# mickey2440.net
KiCad netlist of a schematic drawn in Altium Designer
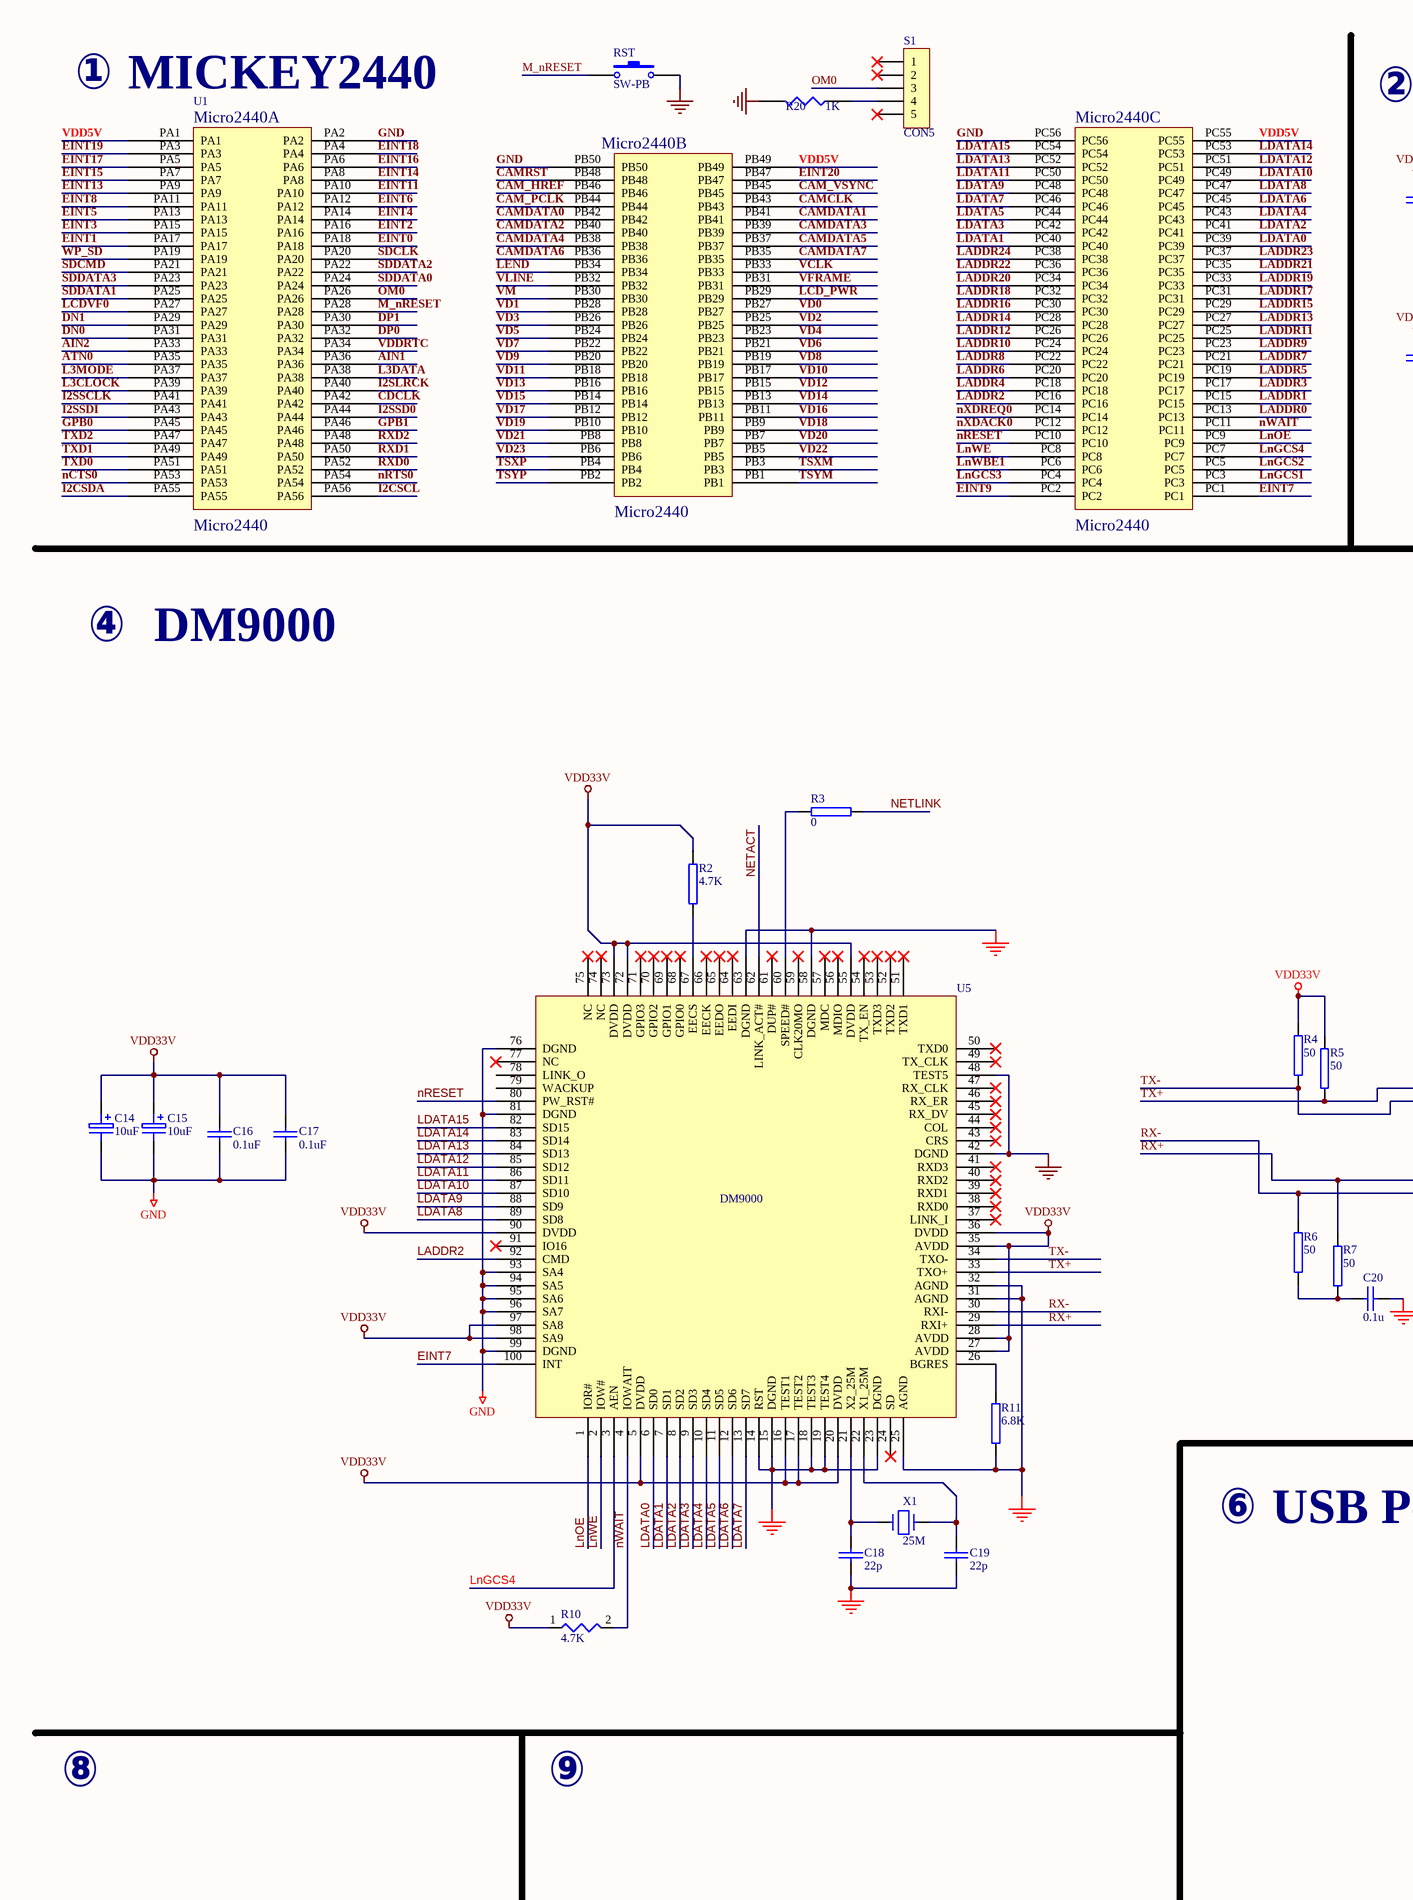
[diagram p0: mickey2440.SchDoc, left]
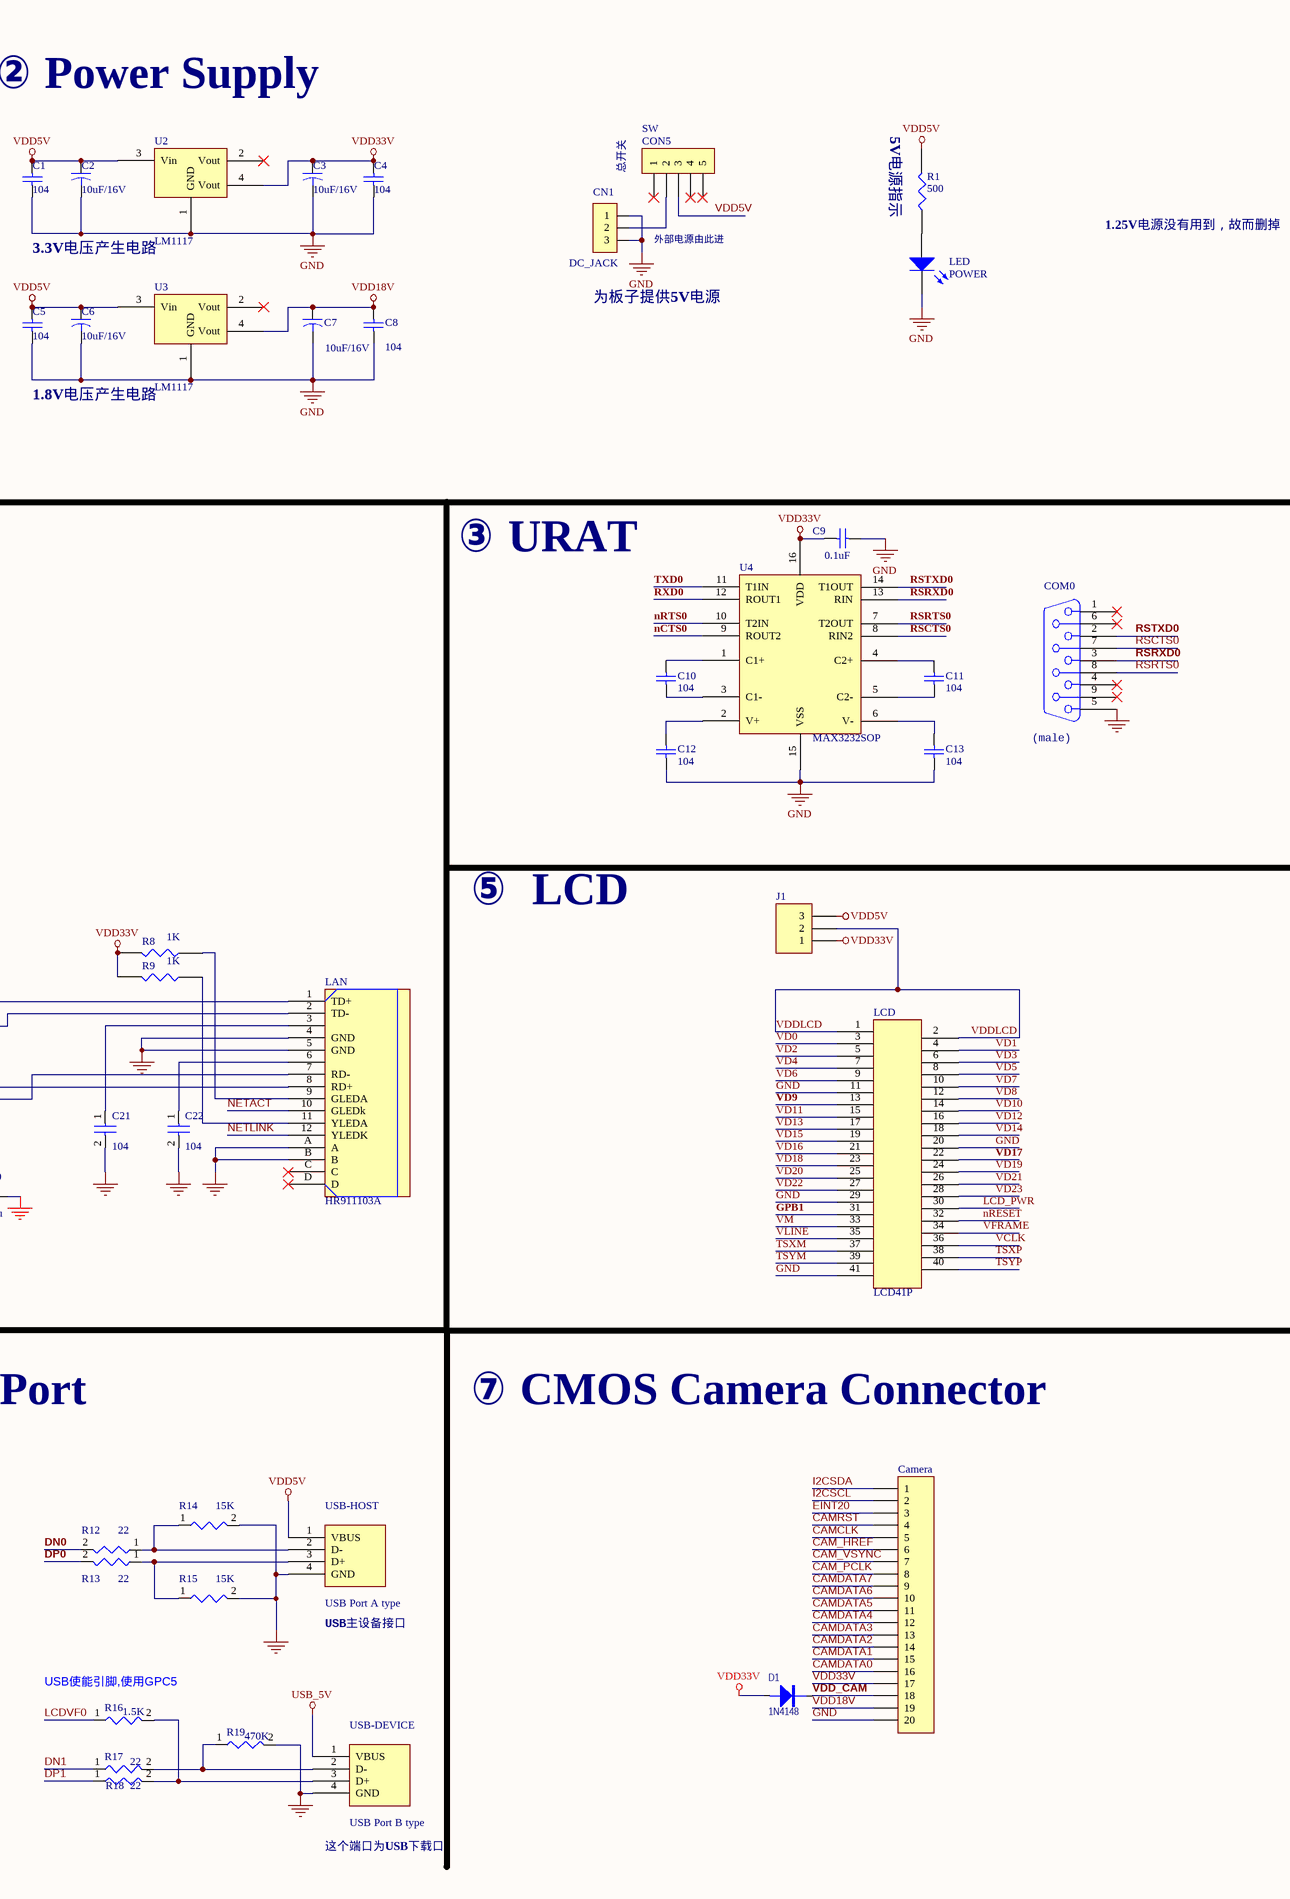
[diagram p1: mickey2440.SchDoc, right]

(export (version "E")
  (design (tool "Eeschema 10.0.6"))
  (components
    (comp (ref "C1")
      (value "104")
      (footprint "0603A")
      (description "Capacitor")
      (fields (field (name "Comment") "Cap") (field (name "PUBLISHER") "Altium Limited"))
      (libsource (lib "Miscellaneous Devices") (part "Cap"))
    )
    (comp (ref "C2")
      (value "10uF/16V")
      (footprint "C3216")
      (description "Capacitor")
      (fields (field (name "Comment") "Cap2") (field (name "PUBLISHER") "Altium Limited"))
      (libsource (lib "Miscellaneous Devices") (part "Cap2"))
    )
    (comp (ref "C3")
      (value "10uF/16V")
      (footprint "C3216")
      (description "Capacitor")
      (fields (field (name "Comment") "Cap2") (field (name "PUBLISHER") "Altium Limited"))
      (libsource (lib "Miscellaneous Devices") (part "Cap2"))
    )
    (comp (ref "C4")
      (value "104")
      (footprint "0603A")
      (description "Capacitor")
      (fields (field (name "Comment") "Cap") (field (name "PUBLISHER") "Altium Limited"))
      (libsource (lib "Miscellaneous Devices") (part "Cap"))
    )
    (comp (ref "C5")
      (value "104")
      (footprint "0603A")
      (description "Capacitor")
      (fields (field (name "Comment") "Cap") (field (name "PUBLISHER") "Altium Limited"))
      (libsource (lib "Miscellaneous Devices") (part "Cap"))
    )
    (comp (ref "C6")
      (value "10uF/16V")
      (footprint "C3216")
      (description "Capacitor")
      (fields (field (name "Comment") "Cap2") (field (name "PUBLISHER") "Altium Limited"))
      (libsource (lib "Miscellaneous Devices") (part "Cap2"))
    )
    (comp (ref "C7")
      (value "10uF/16V")
      (footprint "C3216")
      (description "Capacitor")
      (fields (field (name "Comment") "Cap2") (field (name "PUBLISHER") "Altium Limited"))
      (libsource (lib "Miscellaneous Devices") (part "Cap2"))
    )
    (comp (ref "C8")
      (value "104")
      (footprint "0603A")
      (description "Capacitor")
      (fields (field (name "Comment") "Cap") (field (name "PUBLISHER") "Altium Limited"))
      (libsource (lib "Miscellaneous Devices") (part "Cap"))
    )
    (comp (ref "C9")
      (value "0.1uF")
      (footprint "0603A")
      (description "Capacitor (Semiconductor SIM Model)")
      (fields (field (name "Comment") "Cap Semi") (field (name "PUBLISHER") "Altium Limited"))
      (libsource (lib "Miscellaneous Devices") (part "Cap Semi"))
    )
    (comp (ref "C10")
      (value "104")
      (footprint "0603A")
      (description "Capacitor (Semiconductor SIM Model)")
      (fields (field (name "Comment") "Cap Semi") (field (name "PUBLISHER") "Altium Limited"))
      (libsource (lib "Miscellaneous Devices") (part "Cap Semi"))
    )
    (comp (ref "C11")
      (value "104")
      (footprint "0603A")
      (description "Capacitor (Semiconductor SIM Model)")
      (fields (field (name "Comment") "Cap Semi") (field (name "PUBLISHER") "Altium Limited"))
      (libsource (lib "Miscellaneous Devices") (part "Cap Semi"))
    )
    (comp (ref "C12")
      (value "104")
      (footprint "0603A")
      (description "Capacitor (Semiconductor SIM Model)")
      (fields (field (name "Comment") "Cap Semi") (field (name "PUBLISHER") "Altium Limited"))
      (libsource (lib "Miscellaneous Devices") (part "Cap Semi"))
    )
    (comp (ref "C13")
      (value "104")
      (footprint "0603A")
      (description "Capacitor (Semiconductor SIM Model)")
      (fields (field (name "Comment") "Cap Semi") (field (name "PUBLISHER") "Altium Limited"))
      (libsource (lib "Miscellaneous Devices") (part "Cap Semi"))
    )
    (comp (ref "C14") (value "10uF") (footprint "C3216") (libsource (lib "*") (part "ELECTRO1")))
    (comp (ref "C15") (value "10uF") (footprint "C3216") (libsource (lib "*") (part "ELECTRO1")))
    (comp (ref "C16") (value "0.1uF") (footprint "0603A") (libsource (lib "*") (part "CAP")))
    (comp (ref "C17") (value "0.1uF") (footprint "0603A") (libsource (lib "*") (part "CAP")))
    (comp (ref "C18") (value "22p") (footprint "0603A") (libsource (lib "*") (part "CAP")))
    (comp (ref "C19") (value "22p") (footprint "0603A") (libsource (lib "*") (part "CAP")))
    (comp (ref "C20") (value "0.1u") (footprint "0603A") (libsource (lib "*") (part "CAP")))
    (comp (ref "C21") (value "104") (footprint "0603A") (libsource (lib "*") (part "CAP NP_0")))
    (comp (ref "C22") (value "104") (footprint "0603A") (libsource (lib "*") (part "CAP NP_0")))
    (comp (ref "Camera")
      (value "CON20")
      (footprint "IDC20SS")
      (description "Connector")
      (libsource (lib "*") (part "CON20"))
    )
    (comp (ref "CN1") (value "DC_JACK") (footprint "DC25") (libsource (lib "*") (part "CON3")))
    (comp (ref "COM0") (value "~") (footprint "DB9RA/M") (libsource (lib "*") (part "CONNECTOR DB9")))
    (comp (ref "D1") (value "1N4148") (footprint "D1206") (libsource (lib "*") (part "DIODE")))
    (comp (ref "J1")
      (value "~")
      (footprint "HDR1X3")
      (description "Header, 3-Pin")
      (fields (field (name "PUBLISHER") "Altium Limited"))
      (libsource (lib "Miscellaneous Connectors") (part "Header 3"))
    )
    (comp (ref "LAN") (value "HR911103A") (footprint "HR911103A") (libsource (lib "*") (part "HR911103A")))
    (comp (ref "LCD") (value "LCD41P") (footprint "DF9B-41P-1V2") (libsource (lib "*") (part "LCD41P")))
    (comp (ref "LED")
      (value "POWER")
      (footprint "LED")
      (description "Typical BLUE SiC LED")
      (fields (field (name "PUBLISHER") "Altium Limited"))
      (libsource (lib "Miscellaneous Devices") (part "LED3"))
    )
    (comp (ref "R1") (value "500") (footprint "0603R") (libsource (lib "*") (part "RES1")))
    (comp (ref "R2") (value "4.7K") (footprint "0603R") (libsource (lib "*") (part "RES2")))
    (comp (ref "R3") (value "0") (footprint "0603R") (libsource (lib "*") (part "RES2")))
    (comp (ref "R4") (value "50") (footprint "0603R") (libsource (lib "*") (part "RES2")))
    (comp (ref "R5") (value "50") (footprint "0603R") (libsource (lib "*") (part "RES2")))
    (comp (ref "R6") (value "50") (footprint "0603R") (libsource (lib "*") (part "RES2")))
    (comp (ref "R7") (value "50") (footprint "0603R") (libsource (lib "*") (part "RES2")))
    (comp (ref "R8") (value "1K") (footprint "0603R") (libsource (lib "*") (part "RES1")))
    (comp (ref "R9") (value "1K") (footprint "0603R") (libsource (lib "*") (part "RES1")))
    (comp (ref "R10") (value "4.7K") (footprint "0603R") (libsource (lib "*") (part "R_0")))
    (comp (ref "R11") (value "6.8K") (footprint "0603R") (libsource (lib "*") (part "RES2")))
    (comp (ref "R12") (value "22") (footprint "0603R") (libsource (lib "*") (part "RESISTOR_2")))
    (comp (ref "R13") (value "22") (footprint "0603R") (libsource (lib "*") (part "RESISTOR_2")))
    (comp (ref "R14") (value "15K") (footprint "0603R") (libsource (lib "*") (part "RESISTOR_2")))
    (comp (ref "R15") (value "15K") (footprint "0603R") (libsource (lib "*") (part "RESISTOR_2")))
    (comp (ref "R16") (value "1.5K") (footprint "0603R") (libsource (lib "*") (part "RESISTOR_2")))
    (comp (ref "R17") (value "22") (footprint "0603R") (libsource (lib "*") (part "RESISTOR_2")))
    (comp (ref "R18") (value "22") (footprint "0603R") (libsource (lib "*") (part "RESISTOR_2")))
    (comp (ref "R19") (value "470K") (footprint "0603R") (libsource (lib "*") (part "RESISTOR_2")))
    (comp (ref "R20") (value "1K") (footprint "0603R") (libsource (lib "*") (part "RES1")))
    (comp (ref "RST")
      (value "SW-PB")
      (footprint "RST")
      (description "Switch")
      (fields (field (name "PUBLISHER") "Altium Limited"))
      (libsource (lib "Miscellaneous Devices") (part "SW-PB"))
    )
    (comp (ref "S1")
      (value "CON5")
      (footprint "PCBComponent_1")
      (description "Connector")
      (libsource (lib "*") (part "CON5"))
    )
    (comp (ref "SW")
      (value "CON5")
      (footprint "Micro2440_LIB:PCBComponent_1")
      (description "Connector")
      (libsource (lib "") (part "CON5_1"))
    )
    (comp (ref "U1")
      (value "Micro2440")
      (footprint "Micro2440SDK:MICRO2440")
      (libsource (lib "MICRO2440_01") (part "Component_1"))
    )
    (comp (ref "U2")
      (value "LM1117")
      (footprint "2440_LIB:SOT223S")
      (libsource (lib "MICRO2440_LIB") (part "LM1117"))
    )
    (comp (ref "U3") (value "LM1117") (footprint "SOT223S") (libsource (lib "MICRO2440_LIB") (part "LM1117")))
    (comp (ref "U4")
      (value "MAX3232SOP")
      (footprint "SSOP16")
      (libsource (lib "MAX3232SOP") (part "Component_1"))
    )
    (comp (ref "U5") (value "DM9000") (footprint "QFP100") (libsource (lib "*") (part "DM9000")))
    (comp (ref "USB-DEVICE")
      (value "USB Port B type")
      (footprint "USB-B")
      (libsource (lib "*") (part "USBPORT"))
    )
    (comp (ref "USB-HOST")
      (value "USB Port A type")
      (footprint "USB-A")
      (libsource (lib "*") (part "USBPORT"))
    )
    (comp (ref "X1") (value "25M") (footprint "OSC2PR-1") (libsource (lib "*") (part "CRYSTAL")))
  )
  (nets
    (net (code "1") (name "/AIN1") (class "Default")
      (node (ref "U1") (pin "PA36") (pinfunction "PA36_PA36") (pintype "passive"))
    )
    (net (code "2") (name "/AIN2") (class "Default")
      (node (ref "U1") (pin "PA33") (pinfunction "PA33_PA33") (pintype "passive"))
    )
    (net (code "3") (name "/ATN0") (class "Default")
      (node (ref "U1") (pin "PA35") (pinfunction "PA35_PA35") (pintype "passive"))
    )
    (net (code "4") (name "/CAMCLK") (class "Default")
      (node (ref "Camera") (pin "5") (pinfunction "5_5") (pintype "passive"))
      (node (ref "U1") (pin "PB43") (pinfunction "PB43_PB43") (pintype "passive"))
    )
    (net (code "5") (name "/CAMDATA0") (class "Default")
      (node (ref "Camera") (pin "16") (pinfunction "16_16") (pintype "passive"))
      (node (ref "U1") (pin "PB42") (pinfunction "PB42_PB42") (pintype "passive"))
    )
    (net (code "6") (name "/CAMDATA1") (class "Default")
      (node (ref "Camera") (pin "15") (pinfunction "15_15") (pintype "passive"))
      (node (ref "U1") (pin "PB41") (pinfunction "PB41_PB41") (pintype "passive"))
    )
    (net (code "7") (name "/CAMDATA2") (class "Default")
      (node (ref "Camera") (pin "14") (pinfunction "14_14") (pintype "passive"))
      (node (ref "U1") (pin "PB40") (pinfunction "PB40_PB40") (pintype "passive"))
    )
    (net (code "8") (name "/CAMDATA3") (class "Default")
      (node (ref "Camera") (pin "13") (pinfunction "13_13") (pintype "passive"))
      (node (ref "U1") (pin "PB39") (pinfunction "PB39_PB39") (pintype "passive"))
    )
    (net (code "9") (name "/CAMDATA4") (class "Default")
      (node (ref "Camera") (pin "12") (pinfunction "12_12") (pintype "passive"))
      (node (ref "U1") (pin "PB38") (pinfunction "PB38_PB38") (pintype "passive"))
    )
    (net (code "10") (name "/CAMDATA5") (class "Default")
      (node (ref "Camera") (pin "11") (pinfunction "11_11") (pintype "passive"))
      (node (ref "U1") (pin "PB37") (pinfunction "PB37_PB37") (pintype "passive"))
    )
    (net (code "11") (name "/CAMDATA6") (class "Default")
      (node (ref "Camera") (pin "10") (pinfunction "10_10") (pintype "passive"))
      (node (ref "U1") (pin "PB36") (pinfunction "PB36_PB36") (pintype "passive"))
    )
    (net (code "12") (name "/CAMDATA7") (class "Default")
      (node (ref "Camera") (pin "9") (pinfunction "9_9") (pintype "passive"))
      (node (ref "U1") (pin "PB35") (pinfunction "PB35_PB35") (pintype "passive"))
    )
    (net (code "13") (name "/CAMRST") (class "Default")
      (node (ref "Camera") (pin "4") (pinfunction "4_4") (pintype "passive"))
      (node (ref "U1") (pin "PB48") (pinfunction "PB48_PB48") (pintype "passive"))
    )
    (net (code "14") (name "/CAM_HREF") (class "Default")
      (node (ref "Camera") (pin "6") (pinfunction "6_6") (pintype "passive"))
      (node (ref "U1") (pin "PB46") (pinfunction "PB46_PB46") (pintype "passive"))
    )
    (net (code "15") (name "/CAM_PCLK") (class "Default")
      (node (ref "Camera") (pin "8") (pinfunction "8_8") (pintype "passive"))
      (node (ref "U1") (pin "PB44") (pinfunction "PB44_PB44") (pintype "passive"))
    )
    (net (code "16") (name "/CAM_VSYNC") (class "Default")
      (node (ref "Camera") (pin "7") (pinfunction "7_7") (pintype "passive"))
      (node (ref "U1") (pin "PB45") (pinfunction "PB45_PB45") (pintype "passive"))
    )
    (net (code "17") (name "/CDCLK") (class "Default")
      (node (ref "U1") (pin "PA42") (pinfunction "PA42_PA42") (pintype "passive"))
    )
    (net (code "18") (name "/DN0") (class "Default")
      (node (ref "R12") (pin "2") (pinfunction "2_2") (pintype "passive"))
      (node (ref "U1") (pin "PA31") (pinfunction "PA31_PA31") (pintype "passive"))
    )
    (net (code "19") (name "/DN1") (class "Default")
      (node (ref "R17") (pin "1") (pinfunction "1_1") (pintype "passive"))
      (node (ref "U1") (pin "PA29") (pinfunction "PA29_PA29") (pintype "passive"))
    )
    (net (code "20") (name "/DP0") (class "Default")
      (node (ref "R13") (pin "2") (pinfunction "2_2") (pintype "passive"))
      (node (ref "U1") (pin "PA32") (pinfunction "PA32_PA32") (pintype "passive"))
    )
    (net (code "21") (name "/DP1") (class "Default")
      (node (ref "R18") (pin "1") (pinfunction "1_1") (pintype "passive"))
      (node (ref "U1") (pin "PA30") (pinfunction "PA30_PA30") (pintype "passive"))
    )
    (net (code "22") (name "/EINT0") (class "Default")
      (node (ref "U1") (pin "PA18") (pinfunction "PA18_PA18") (pintype "passive"))
    )
    (net (code "23") (name "/EINT1") (class "Default")
      (node (ref "U1") (pin "PA17") (pinfunction "PA17_PA17") (pintype "passive"))
    )
    (net (code "24") (name "/EINT2") (class "Default")
      (node (ref "U1") (pin "PA16") (pinfunction "PA16_PA16") (pintype "passive"))
    )
    (net (code "25") (name "/EINT3") (class "Default")
      (node (ref "U1") (pin "PA15") (pinfunction "PA15_PA15") (pintype "passive"))
    )
    (net (code "26") (name "/EINT4") (class "Default")
      (node (ref "U1") (pin "PA14") (pinfunction "PA14_PA14") (pintype "passive"))
    )
    (net (code "27") (name "/EINT5") (class "Default")
      (node (ref "U1") (pin "PA13") (pinfunction "PA13_PA13") (pintype "passive"))
    )
    (net (code "28") (name "/EINT6") (class "Default")
      (node (ref "U1") (pin "PA12") (pinfunction "PA12_PA12") (pintype "passive"))
    )
    (net (code "29") (name "/EINT7") (class "Default")
      (node (ref "U1") (pin "PC1") (pinfunction "PC1_PC1") (pintype "passive"))
      (node (ref "U5") (pin "100") (pinfunction "INT_100") (pintype "passive"))
    )
    (net (code "30") (name "/EINT8") (class "Default")
      (node (ref "U1") (pin "PA11") (pinfunction "PA11_PA11") (pintype "passive"))
    )
    (net (code "31") (name "/EINT9") (class "Default")
      (node (ref "U1") (pin "PC2") (pinfunction "PC2_PC2") (pintype "passive"))
    )
    (net (code "32") (name "/EINT11") (class "Default")
      (node (ref "U1") (pin "PA10") (pinfunction "PA10_PA10") (pintype "passive"))
    )
    (net (code "33") (name "/EINT13") (class "Default")
      (node (ref "U1") (pin "PA9") (pinfunction "PA9_PA9") (pintype "passive"))
    )
    (net (code "34") (name "/EINT14") (class "Default")
      (node (ref "U1") (pin "PA8") (pinfunction "PA8_PA8") (pintype "passive"))
    )
    (net (code "35") (name "/EINT15") (class "Default")
      (node (ref "U1") (pin "PA7") (pinfunction "PA7_PA7") (pintype "passive"))
    )
    (net (code "36") (name "/EINT16") (class "Default")
      (node (ref "U1") (pin "PA6") (pinfunction "PA6_PA6") (pintype "passive"))
    )
    (net (code "37") (name "/EINT17") (class "Default")
      (node (ref "U1") (pin "PA5") (pinfunction "PA5_PA5") (pintype "passive"))
    )
    (net (code "38") (name "/EINT18") (class "Default")
      (node (ref "U1") (pin "PA4") (pinfunction "PA4_PA4") (pintype "passive"))
    )
    (net (code "39") (name "/EINT19") (class "Default")
      (node (ref "U1") (pin "PA3") (pinfunction "PA3_PA3") (pintype "passive"))
    )
    (net (code "40") (name "/EINT20") (class "Default")
      (node (ref "Camera") (pin "3") (pinfunction "3_3") (pintype "passive"))
      (node (ref "U1") (pin "PB47") (pinfunction "PB47_PB47") (pintype "passive"))
    )
    (net (code "41") (name "/GPB0") (class "Default")
      (node (ref "U1") (pin "PA45") (pinfunction "PA45_PA45") (pintype "passive"))
    )
    (net (code "42") (name "/GPB1") (class "Default")
      (node (ref "LCD") (pin "31") (pintype "passive"))
      (node (ref "U1") (pin "PA46") (pinfunction "PA46_PA46") (pintype "passive"))
    )
    (net (code "43") (name "/I2CSCL") (class "Default")
      (node (ref "Camera") (pin "2") (pinfunction "2_2") (pintype "passive"))
      (node (ref "U1") (pin "PA56") (pinfunction "PA56_PA56") (pintype "passive"))
    )
    (net (code "44") (name "/I2CSDA") (class "Default")
      (node (ref "Camera") (pin "1") (pinfunction "1_1") (pintype "passive"))
      (node (ref "U1") (pin "PA55") (pinfunction "PA55_PA55") (pintype "passive"))
    )
    (net (code "45") (name "/I2SLRCK") (class "Default")
      (node (ref "U1") (pin "PA40") (pinfunction "PA40_PA40") (pintype "passive"))
    )
    (net (code "46") (name "/I2SSCLK") (class "Default")
      (node (ref "U1") (pin "PA41") (pinfunction "PA41_PA41") (pintype "passive"))
    )
    (net (code "47") (name "/I2SSD0") (class "Default")
      (node (ref "U1") (pin "PA44") (pinfunction "PA44_PA44") (pintype "passive"))
    )
    (net (code "48") (name "/I2SSDI") (class "Default")
      (node (ref "U1") (pin "PA43") (pinfunction "PA43_PA43") (pintype "passive"))
    )
    (net (code "49") (name "/L3CLOCK") (class "Default")
      (node (ref "U1") (pin "PA39") (pinfunction "PA39_PA39") (pintype "passive"))
    )
    (net (code "50") (name "/L3DATA") (class "Default")
      (node (ref "U1") (pin "PA38") (pinfunction "PA38_PA38") (pintype "passive"))
    )
    (net (code "51") (name "/L3MODE") (class "Default")
      (node (ref "U1") (pin "PA37") (pinfunction "PA37_PA37") (pintype "passive"))
    )
    (net (code "52") (name "/LADDR0") (class "Default")
      (node (ref "U1") (pin "PC13") (pinfunction "PC13_PC13") (pintype "passive"))
    )
    (net (code "53") (name "/LADDR1") (class "Default")
      (node (ref "U1") (pin "PC15") (pinfunction "PC15_PC15") (pintype "passive"))
    )
    (net (code "54") (name "/LADDR2") (class "Default")
      (node (ref "U1") (pin "PC16") (pinfunction "PC16_PC16") (pintype "passive"))
      (node (ref "U5") (pin "92") (pinfunction "CMD_92") (pintype "passive"))
    )
    (net (code "55") (name "/LADDR3") (class "Default")
      (node (ref "U1") (pin "PC17") (pinfunction "PC17_PC17") (pintype "passive"))
    )
    (net (code "56") (name "/LADDR4") (class "Default")
      (node (ref "U1") (pin "PC18") (pinfunction "PC18_PC18") (pintype "passive"))
    )
    (net (code "57") (name "/LADDR5") (class "Default")
      (node (ref "U1") (pin "PC19") (pinfunction "PC19_PC19") (pintype "passive"))
    )
    (net (code "58") (name "/LADDR6") (class "Default")
      (node (ref "U1") (pin "PC20") (pinfunction "PC20_PC20") (pintype "passive"))
    )
    (net (code "59") (name "/LADDR7") (class "Default")
      (node (ref "U1") (pin "PC21") (pinfunction "PC21_PC21") (pintype "passive"))
    )
    (net (code "60") (name "/LADDR8") (class "Default")
      (node (ref "U1") (pin "PC22") (pinfunction "PC22_PC22") (pintype "passive"))
    )
    (net (code "61") (name "/LADDR9") (class "Default")
      (node (ref "U1") (pin "PC23") (pinfunction "PC23_PC23") (pintype "passive"))
    )
    (net (code "62") (name "/LADDR10") (class "Default")
      (node (ref "U1") (pin "PC24") (pinfunction "PC24_PC24") (pintype "passive"))
    )
    (net (code "63") (name "/LADDR11") (class "Default")
      (node (ref "U1") (pin "PC25") (pinfunction "PC25_PC25") (pintype "passive"))
    )
    (net (code "64") (name "/LADDR12") (class "Default")
      (node (ref "U1") (pin "PC26") (pinfunction "PC26_PC26") (pintype "passive"))
    )
    (net (code "65") (name "/LADDR13") (class "Default")
      (node (ref "U1") (pin "PC27") (pinfunction "PC27_PC27") (pintype "passive"))
    )
    (net (code "66") (name "/LADDR14") (class "Default")
      (node (ref "U1") (pin "PC28") (pinfunction "PC28_PC28") (pintype "passive"))
    )
    (net (code "67") (name "/LADDR15") (class "Default")
      (node (ref "U1") (pin "PC29") (pinfunction "PC29_PC29") (pintype "passive"))
    )
    (net (code "68") (name "/LADDR16") (class "Default")
      (node (ref "U1") (pin "PC30") (pinfunction "PC30_PC30") (pintype "passive"))
    )
    (net (code "69") (name "/LADDR17") (class "Default")
      (node (ref "U1") (pin "PC31") (pinfunction "PC31_PC31") (pintype "passive"))
    )
    (net (code "70") (name "/LADDR18") (class "Default")
      (node (ref "U1") (pin "PC32") (pinfunction "PC32_PC32") (pintype "passive"))
    )
    (net (code "71") (name "/LADDR19") (class "Default")
      (node (ref "U1") (pin "PC33") (pinfunction "PC33_PC33") (pintype "passive"))
    )
    (net (code "72") (name "/LADDR20") (class "Default")
      (node (ref "U1") (pin "PC34") (pinfunction "PC34_PC34") (pintype "passive"))
    )
    (net (code "73") (name "/LADDR21") (class "Default")
      (node (ref "U1") (pin "PC35") (pinfunction "PC35_PC35") (pintype "passive"))
    )
    (net (code "74") (name "/LADDR22") (class "Default")
      (node (ref "U1") (pin "PC36") (pinfunction "PC36_PC36") (pintype "passive"))
    )
    (net (code "75") (name "/LADDR23") (class "Default")
      (node (ref "U1") (pin "PC37") (pinfunction "PC37_PC37") (pintype "passive"))
    )
    (net (code "76") (name "/LADDR24") (class "Default")
      (node (ref "U1") (pin "PC38") (pinfunction "PC38_PC38") (pintype "passive"))
    )
    (net (code "77") (name "/LCDVF0") (class "Default")
      (node (ref "R16") (pin "1") (pinfunction "1_1") (pintype "passive"))
      (node (ref "U1") (pin "PA27") (pinfunction "PA27_PA27") (pintype "passive"))
    )
    (net (code "78") (name "/LCD_PWR") (class "Default")
      (node (ref "LCD") (pin "30") (pintype "passive"))
      (node (ref "U1") (pin "PB29") (pinfunction "PB29_PB29") (pintype "passive"))
    )
    (net (code "79") (name "/LDATA0") (class "Default")
      (node (ref "U1") (pin "PC39") (pinfunction "PC39_PC39") (pintype "passive"))
      (node (ref "U5") (pin "6") (pinfunction "SD0_6") (pintype "passive"))
    )
    (net (code "80") (name "/LDATA1") (class "Default")
      (node (ref "U1") (pin "PC40") (pinfunction "PC40_PC40") (pintype "passive"))
      (node (ref "U5") (pin "7") (pinfunction "SD1_7") (pintype "passive"))
    )
    (net (code "81") (name "/LDATA2") (class "Default")
      (node (ref "U1") (pin "PC41") (pinfunction "PC41_PC41") (pintype "passive"))
      (node (ref "U5") (pin "8") (pinfunction "SD2_8") (pintype "passive"))
    )
    (net (code "82") (name "/LDATA3") (class "Default")
      (node (ref "U1") (pin "PC42") (pinfunction "PC42_PC42") (pintype "passive"))
      (node (ref "U5") (pin "9") (pinfunction "SD3_9") (pintype "passive"))
    )
    (net (code "83") (name "/LDATA4") (class "Default")
      (node (ref "U1") (pin "PC43") (pinfunction "PC43_PC43") (pintype "passive"))
      (node (ref "U5") (pin "10") (pinfunction "SD4_10") (pintype "passive"))
    )
    (net (code "84") (name "/LDATA5") (class "Default")
      (node (ref "U1") (pin "PC44") (pinfunction "PC44_PC44") (pintype "passive"))
      (node (ref "U5") (pin "11") (pinfunction "SD5_11") (pintype "passive"))
    )
    (net (code "85") (name "/LDATA6") (class "Default")
      (node (ref "U1") (pin "PC45") (pinfunction "PC45_PC45") (pintype "passive"))
      (node (ref "U5") (pin "12") (pinfunction "SD6_12") (pintype "passive"))
    )
    (net (code "86") (name "/LDATA7") (class "Default")
      (node (ref "U1") (pin "PC46") (pinfunction "PC46_PC46") (pintype "passive"))
      (node (ref "U5") (pin "13") (pinfunction "SD7_13") (pintype "passive"))
    )
    (net (code "87") (name "/LDATA8") (class "Default")
      (node (ref "U1") (pin "PC47") (pinfunction "PC47_PC47") (pintype "passive"))
      (node (ref "U5") (pin "89") (pinfunction "SD8_89") (pintype "passive"))
    )
    (net (code "88") (name "/LDATA9") (class "Default")
      (node (ref "U1") (pin "PC48") (pinfunction "PC48_PC48") (pintype "passive"))
      (node (ref "U5") (pin "88") (pinfunction "SD9_88") (pintype "passive"))
    )
    (net (code "89") (name "/LDATA10") (class "Default")
      (node (ref "U1") (pin "PC49") (pinfunction "PC49_PC49") (pintype "passive"))
      (node (ref "U5") (pin "87") (pinfunction "SD10_87") (pintype "passive"))
    )
    (net (code "90") (name "/LDATA11") (class "Default")
      (node (ref "U1") (pin "PC50") (pinfunction "PC50_PC50") (pintype "passive"))
      (node (ref "U5") (pin "86") (pinfunction "SD11_86") (pintype "passive"))
    )
    (net (code "91") (name "/LDATA12") (class "Default")
      (node (ref "U1") (pin "PC51") (pinfunction "PC51_PC51") (pintype "passive"))
      (node (ref "U5") (pin "85") (pinfunction "SD12_85") (pintype "passive"))
    )
    (net (code "92") (name "/LDATA13") (class "Default")
      (node (ref "U1") (pin "PC52") (pinfunction "PC52_PC52") (pintype "passive"))
      (node (ref "U5") (pin "84") (pinfunction "SD13_84") (pintype "passive"))
    )
    (net (code "93") (name "/LDATA14") (class "Default")
      (node (ref "U1") (pin "PC53") (pinfunction "PC53_PC53") (pintype "passive"))
      (node (ref "U5") (pin "83") (pinfunction "SD14_83") (pintype "passive"))
    )
    (net (code "94") (name "/LDATA15") (class "Default")
      (node (ref "U1") (pin "PC54") (pinfunction "PC54_PC54") (pintype "passive"))
      (node (ref "U5") (pin "82") (pinfunction "SD15_82") (pintype "passive"))
    )
    (net (code "95") (name "/LEND") (class "Default")
      (node (ref "U1") (pin "PB34") (pinfunction "PB34_PB34") (pintype "passive"))
    )
    (net (code "96") (name "/LnGCS1") (class "Default")
      (node (ref "U1") (pin "PC3") (pinfunction "PC3_PC3") (pintype "passive"))
    )
    (net (code "97") (name "/LnGCS2") (class "Default")
      (node (ref "U1") (pin "PC5") (pinfunction "PC5_PC5") (pintype "passive"))
    )
    (net (code "98") (name "/LnGCS3") (class "Default")
      (node (ref "U1") (pin "PC4") (pinfunction "PC4_PC4") (pintype "passive"))
    )
    (net (code "99") (name "/LnGCS4") (class "Default")
      (node (ref "U1") (pin "PC7") (pinfunction "PC7_PC7") (pintype "passive"))
      (node (ref "U5") (pin "3") (pinfunction "AEN_3") (pintype "passive"))
    )
    (net (code "100") (name "/LnOE") (class "Default")
      (node (ref "U1") (pin "PC9") (pinfunction "PC9_PC9") (pintype "passive"))
      (node (ref "U5") (pin "1") (pinfunction "IOR#_1") (pintype "passive"))
    )
    (net (code "101") (name "/LnWBE1") (class "Default")
      (node (ref "U1") (pin "PC6") (pinfunction "PC6_PC6") (pintype "passive"))
    )
    (net (code "102") (name "/LnWE") (class "Default")
      (node (ref "U1") (pin "PC8") (pinfunction "PC8_PC8") (pintype "passive"))
      (node (ref "U5") (pin "2") (pinfunction "IOW#_2") (pintype "passive"))
    )
    (net (code "103") (name "/M_nRESET") (class "Default")
      (node (ref "RST") (pin "1") (pinfunction "1_1") (pintype "passive"))
      (node (ref "U1") (pin "PA28") (pinfunction "PA28_PA28") (pintype "passive"))
    )
    (net (code "104") (name "/NETACT") (class "Default")
      (node (ref "LAN") (pin "10") (pinfunction "GLEDk_10") (pintype "passive"))
      (node (ref "U5") (pin "62") (pinfunction "LINK_ACT#_62") (pintype "passive"))
    )
    (net (code "105") (name "/NETLINK") (class "Default")
      (node (ref "LAN") (pin "12") (pinfunction "YLEDK_12") (pintype "passive"))
      (node (ref "R3") (pin "1") (pintype "passive"))
    )
    (net (code "106") (name "/OM0") (class "Default")
      (node (ref "S1") (pin "3") (pinfunction "3_3") (pintype "passive"))
      (node (ref "U1") (pin "PA26") (pinfunction "PA26_PA26") (pintype "passive"))
    )
    (net (code "107") (name "/RSCTS0") (class "Default")
      (node (ref "COM0") (pin "7") (pinfunction "7_7") (pintype "passive"))
      (node (ref "U4") (pin "8") (pinfunction "RIN2_8") (pintype "passive"))
    )
    (net (code "108") (name "/RSRTS0") (class "Default")
      (node (ref "COM0") (pin "8") (pinfunction "8_8") (pintype "passive"))
      (node (ref "U4") (pin "7") (pinfunction "T2OUT_7") (pintype "passive"))
    )
    (net (code "109") (name "/RSRXD0") (class "Default")
      (node (ref "COM0") (pin "3") (pinfunction "3_3") (pintype "passive"))
      (node (ref "U4") (pin "13") (pinfunction "RIN_13") (pintype "passive"))
    )
    (net (code "110") (name "/RSTXD0") (class "Default")
      (node (ref "COM0") (pin "2") (pinfunction "2_2") (pintype "passive"))
      (node (ref "U4") (pin "14") (pinfunction "T1OUT_14") (pintype "passive"))
    )
    (net (code "111") (name "/RX+") (class "Default")
      (node (ref "LAN") (pin "8") (pinfunction "RD+_8") (pintype "passive"))
      (node (ref "R7") (pin "2") (pintype "passive"))
      (node (ref "U5") (pin "29") (pinfunction "RXI+_29") (pintype "passive"))
    )
    (net (code "112") (name "/RX-") (class "Default")
      (node (ref "LAN") (pin "7") (pinfunction "RD-_7") (pintype "passive"))
      (node (ref "R6") (pin "2") (pintype "passive"))
      (node (ref "U5") (pin "30") (pinfunction "RXI-_30") (pintype "passive"))
    )
    (net (code "113") (name "/RXD0") (class "Default")
      (node (ref "U1") (pin "PA52") (pinfunction "PA52_PA52") (pintype "passive"))
      (node (ref "U4") (pin "12") (pinfunction "ROUT1_12") (pintype "passive"))
    )
    (net (code "114") (name "/RXD1") (class "Default")
      (node (ref "U1") (pin "PA50") (pinfunction "PA50_PA50") (pintype "passive"))
    )
    (net (code "115") (name "/RXD2") (class "Default")
      (node (ref "U1") (pin "PA48") (pinfunction "PA48_PA48") (pintype "passive"))
    )
    (net (code "116") (name "/SDCLK") (class "Default")
      (node (ref "U1") (pin "PA20") (pinfunction "PA20_PA20") (pintype "passive"))
    )
    (net (code "117") (name "/SDCMD") (class "Default")
      (node (ref "U1") (pin "PA21") (pinfunction "PA21_PA21") (pintype "passive"))
    )
    (net (code "118") (name "/SDDATA0") (class "Default")
      (node (ref "U1") (pin "PA24") (pinfunction "PA24_PA24") (pintype "passive"))
    )
    (net (code "119") (name "/SDDATA1") (class "Default")
      (node (ref "U1") (pin "PA25") (pinfunction "PA25_PA25") (pintype "passive"))
    )
    (net (code "120") (name "/SDDATA2") (class "Default")
      (node (ref "U1") (pin "PA22") (pinfunction "PA22_PA22") (pintype "passive"))
    )
    (net (code "121") (name "/SDDATA3") (class "Default")
      (node (ref "U1") (pin "PA23") (pinfunction "PA23_PA23") (pintype "passive"))
    )
    (net (code "122") (name "/TSXM") (class "Default")
      (node (ref "LCD") (pin "37") (pintype "passive"))
      (node (ref "U1") (pin "PB3") (pinfunction "PB3_PB3") (pintype "passive"))
    )
    (net (code "123") (name "/TSXP") (class "Default")
      (node (ref "LCD") (pin "38") (pintype "passive"))
      (node (ref "U1") (pin "PB4") (pinfunction "PB4_PB4") (pintype "passive"))
    )
    (net (code "124") (name "/TSYM") (class "Default")
      (node (ref "LCD") (pin "39") (pintype "passive"))
      (node (ref "U1") (pin "PB1") (pinfunction "PB1_PB1") (pintype "passive"))
    )
    (net (code "125") (name "/TSYP") (class "Default")
      (node (ref "LCD") (pin "40") (pintype "passive"))
      (node (ref "U1") (pin "PB2") (pinfunction "PB2_PB2") (pintype "passive"))
    )
    (net (code "126") (name "/TX+") (class "Default")
      (node (ref "LAN") (pin "1") (pinfunction "TD+_1") (pintype "passive"))
      (node (ref "R5") (pin "1") (pintype "passive"))
      (node (ref "U5") (pin "33") (pinfunction "TXO+_33") (pintype "passive"))
    )
    (net (code "127") (name "/TX-") (class "Default")
      (node (ref "LAN") (pin "2") (pinfunction "TD-_2") (pintype "passive"))
      (node (ref "R4") (pin "1") (pintype "passive"))
      (node (ref "U5") (pin "34") (pinfunction "TXO-_34") (pintype "passive"))
    )
    (net (code "128") (name "/TXD0") (class "Default")
      (node (ref "U1") (pin "PA51") (pinfunction "PA51_PA51") (pintype "passive"))
      (node (ref "U4") (pin "11") (pinfunction "T1IN_11") (pintype "passive"))
    )
    (net (code "129") (name "/TXD1") (class "Default")
      (node (ref "U1") (pin "PA49") (pinfunction "PA49_PA49") (pintype "passive"))
    )
    (net (code "130") (name "/TXD2") (class "Default")
      (node (ref "U1") (pin "PA47") (pinfunction "PA47_PA47") (pintype "passive"))
    )
    (net (code "131") (name "/VCLK") (class "Default")
      (node (ref "LCD") (pin "36") (pintype "passive"))
      (node (ref "U1") (pin "PB33") (pinfunction "PB33_PB33") (pintype "passive"))
    )
    (net (code "132") (name "/VD0") (class "Default")
      (node (ref "LCD") (pin "3") (pintype "passive"))
      (node (ref "U1") (pin "PB27") (pinfunction "PB27_PB27") (pintype "passive"))
    )
    (net (code "133") (name "/VD1") (class "Default")
      (node (ref "LCD") (pin "4") (pintype "passive"))
      (node (ref "U1") (pin "PB28") (pinfunction "PB28_PB28") (pintype "passive"))
    )
    (net (code "134") (name "/VD2") (class "Default")
      (node (ref "LCD") (pin "5") (pintype "passive"))
      (node (ref "U1") (pin "PB25") (pinfunction "PB25_PB25") (pintype "passive"))
    )
    (net (code "135") (name "/VD3") (class "Default")
      (node (ref "LCD") (pin "6") (pintype "passive"))
      (node (ref "U1") (pin "PB26") (pinfunction "PB26_PB26") (pintype "passive"))
    )
    (net (code "136") (name "/VD4") (class "Default")
      (node (ref "LCD") (pin "7") (pintype "passive"))
      (node (ref "U1") (pin "PB23") (pinfunction "PB23_PB23") (pintype "passive"))
    )
    (net (code "137") (name "/VD5") (class "Default")
      (node (ref "LCD") (pin "8") (pintype "passive"))
      (node (ref "U1") (pin "PB24") (pinfunction "PB24_PB24") (pintype "passive"))
    )
    (net (code "138") (name "/VD6") (class "Default")
      (node (ref "LCD") (pin "9") (pintype "passive"))
      (node (ref "U1") (pin "PB21") (pinfunction "PB21_PB21") (pintype "passive"))
    )
    (net (code "139") (name "/VD7") (class "Default")
      (node (ref "LCD") (pin "10") (pintype "passive"))
      (node (ref "U1") (pin "PB22") (pinfunction "PB22_PB22") (pintype "passive"))
    )
    (net (code "140") (name "/VD8") (class "Default")
      (node (ref "LCD") (pin "12") (pintype "passive"))
      (node (ref "U1") (pin "PB19") (pinfunction "PB19_PB19") (pintype "passive"))
    )
    (net (code "141") (name "/VD9") (class "Default")
      (node (ref "LCD") (pin "13") (pintype "passive"))
      (node (ref "U1") (pin "PB20") (pinfunction "PB20_PB20") (pintype "passive"))
    )
    (net (code "142") (name "/VD10") (class "Default")
      (node (ref "LCD") (pin "14") (pintype "passive"))
      (node (ref "U1") (pin "PB17") (pinfunction "PB17_PB17") (pintype "passive"))
    )
    (net (code "143") (name "/VD11") (class "Default")
      (node (ref "LCD") (pin "15") (pintype "passive"))
      (node (ref "U1") (pin "PB18") (pinfunction "PB18_PB18") (pintype "passive"))
    )
    (net (code "144") (name "/VD12") (class "Default")
      (node (ref "LCD") (pin "16") (pintype "passive"))
      (node (ref "U1") (pin "PB15") (pinfunction "PB15_PB15") (pintype "passive"))
    )
    (net (code "145") (name "/VD13") (class "Default")
      (node (ref "LCD") (pin "17") (pintype "passive"))
      (node (ref "U1") (pin "PB16") (pinfunction "PB16_PB16") (pintype "passive"))
    )
    (net (code "146") (name "/VD14") (class "Default")
      (node (ref "LCD") (pin "18") (pintype "passive"))
      (node (ref "U1") (pin "PB13") (pinfunction "PB13_PB13") (pintype "passive"))
    )
    (net (code "147") (name "/VD15") (class "Default")
      (node (ref "LCD") (pin "19") (pintype "passive"))
      (node (ref "U1") (pin "PB14") (pinfunction "PB14_PB14") (pintype "passive"))
    )
    (net (code "148") (name "/VD16") (class "Default")
      (node (ref "LCD") (pin "21") (pintype "passive"))
      (node (ref "U1") (pin "PB11") (pinfunction "PB11_PB11") (pintype "passive"))
    )
    (net (code "149") (name "/VD17") (class "Default")
      (node (ref "LCD") (pin "22") (pintype "passive"))
      (node (ref "U1") (pin "PB12") (pinfunction "PB12_PB12") (pintype "passive"))
    )
    (net (code "150") (name "/VD18") (class "Default")
      (node (ref "LCD") (pin "23") (pintype "passive"))
      (node (ref "U1") (pin "PB9") (pinfunction "PB9_PB9") (pintype "passive"))
    )
    (net (code "151") (name "/VD19") (class "Default")
      (node (ref "LCD") (pin "24") (pintype "passive"))
      (node (ref "U1") (pin "PB10") (pinfunction "PB10_PB10") (pintype "passive"))
    )
    (net (code "152") (name "/VD20") (class "Default")
      (node (ref "LCD") (pin "25") (pintype "passive"))
      (node (ref "U1") (pin "PB7") (pinfunction "PB7_PB7") (pintype "passive"))
    )
    (net (code "153") (name "/VD21") (class "Default")
      (node (ref "LCD") (pin "26") (pintype "passive"))
      (node (ref "U1") (pin "PB8") (pinfunction "PB8_PB8") (pintype "passive"))
    )
    (net (code "154") (name "/VD22") (class "Default")
      (node (ref "LCD") (pin "27") (pintype "passive"))
      (node (ref "U1") (pin "PB5") (pinfunction "PB5_PB5") (pintype "passive"))
    )
    (net (code "155") (name "/VD23") (class "Default")
      (node (ref "LCD") (pin "28") (pintype "passive"))
      (node (ref "U1") (pin "PB6") (pinfunction "PB6_PB6") (pintype "passive"))
    )
    (net (code "156") (name "/VDDLCD") (class "Default")
      (node (ref "J1") (pin "2") (pinfunction "2_2") (pintype "passive"))
      (node (ref "LCD") (pin "1") (pintype "passive"))
      (node (ref "LCD") (pin "2") (pintype "passive"))
    )
    (net (code "157") (name "/VDDRTC") (class "Default")
      (node (ref "U1") (pin "PA34") (pinfunction "PA34_PA34") (pintype "passive"))
    )
    (net (code "158") (name "/VDD_CAM") (class "Default")
      (node (ref "Camera") (pin "18") (pinfunction "18_18") (pintype "passive"))
      (node (ref "D1") (pin "2") (pinfunction "2_2") (pintype "passive"))
    )
    (net (code "159") (name "/VFRAME") (class "Default")
      (node (ref "LCD") (pin "34") (pintype "passive"))
      (node (ref "U1") (pin "PB31") (pinfunction "PB31_PB31") (pintype "passive"))
    )
    (net (code "160") (name "/VLINE") (class "Default")
      (node (ref "LCD") (pin "35") (pintype "passive"))
      (node (ref "U1") (pin "PB32") (pinfunction "PB32_PB32") (pintype "passive"))
    )
    (net (code "161") (name "/VM") (class "Default")
      (node (ref "LCD") (pin "33") (pintype "passive"))
      (node (ref "U1") (pin "PB30") (pinfunction "PB30_PB30") (pintype "passive"))
    )
    (net (code "162") (name "/WP_SD") (class "Default")
      (node (ref "U1") (pin "PA19") (pinfunction "PA19_PA19") (pintype "passive"))
    )
    (net (code "163") (name "/nCTS0") (class "Default")
      (node (ref "U1") (pin "PA53") (pinfunction "PA53_PA53") (pintype "passive"))
      (node (ref "U4") (pin "9") (pinfunction "ROUT2_9") (pintype "passive"))
    )
    (net (code "164") (name "/nRESET") (class "Default")
      (node (ref "LCD") (pin "32") (pintype "passive"))
      (node (ref "U1") (pin "PC10") (pinfunction "PC10_PC10") (pintype "passive"))
      (node (ref "U5") (pin "80") (pinfunction "PW_RST#_80") (pintype "passive"))
    )
    (net (code "165") (name "/nRTS0") (class "Default")
      (node (ref "U1") (pin "PA54") (pinfunction "PA54_PA54") (pintype "passive"))
      (node (ref "U4") (pin "10") (pinfunction "T2IN_10") (pintype "passive"))
    )
    (net (code "166") (name "/nWAIT") (class "Default")
      (node (ref "R10") (pin "2") (pinfunction "2_2") (pintype "passive"))
      (node (ref "U1") (pin "PC11") (pinfunction "PC11_PC11") (pintype "passive"))
      (node (ref "U5") (pin "4") (pinfunction "IOWAIT_4") (pintype "passive"))
    )
    (net (code "167") (name "/nXDACK0") (class "Default")
      (node (ref "U1") (pin "PC12") (pinfunction "PC12_PC12") (pintype "passive"))
    )
    (net (code "168") (name "/nXDREQ0") (class "Default")
      (node (ref "U1") (pin "PC14") (pinfunction "PC14_PC14") (pintype "passive"))
    )
    (net (code "169") (name "GND") (class "Default")
      (node (ref "C1") (pin "2") (pinfunction "2_2") (pintype "passive"))
      (node (ref "C12") (pin "1") (pinfunction "1_1") (pintype "passive"))
      (node (ref "C13") (pin "1") (pinfunction "1_1") (pintype "passive"))
      (node (ref "C14") (pin "2") (pintype "passive"))
      (node (ref "C15") (pin "2") (pintype "passive"))
      (node (ref "C16") (pin "2") (pintype "passive"))
      (node (ref "C17") (pin "2") (pintype "passive"))
      (node (ref "C18") (pin "2") (pintype "passive"))
      (node (ref "C19") (pin "2") (pintype "passive"))
      (node (ref "C2") (pin "2") (pinfunction "2_2") (pintype "passive"))
      (node (ref "C20") (pin "2") (pintype "passive"))
      (node (ref "C21") (pin "2") (pinfunction "2_2") (pintype "passive"))
      (node (ref "C22") (pin "2") (pinfunction "2_2") (pintype "passive"))
      (node (ref "C3") (pin "2") (pinfunction "2_2") (pintype "passive"))
      (node (ref "C4") (pin "2") (pinfunction "2_2") (pintype "passive"))
      (node (ref "C5") (pin "2") (pinfunction "2_2") (pintype "passive"))
      (node (ref "C6") (pin "2") (pinfunction "2_2") (pintype "passive"))
      (node (ref "C7") (pin "2") (pinfunction "2_2") (pintype "passive"))
      (node (ref "C8") (pin "2") (pinfunction "2_2") (pintype "passive"))
      (node (ref "C9") (pin "2") (pinfunction "2_2") (pintype "passive"))
      (node (ref "CN1") (pin "1") (pinfunction "1_1") (pintype "passive"))
      (node (ref "CN1") (pin "3") (pinfunction "3_3") (pintype "passive"))
      (node (ref "COM0") (pin "5") (pinfunction "5_5") (pintype "passive"))
      (node (ref "Camera") (pin "20") (pinfunction "20_20") (pintype "passive"))
      (node (ref "LAN") (pin "4") (pinfunction "GND_4") (pintype "passive"))
      (node (ref "LAN") (pin "5") (pinfunction "GND_5") (pintype "passive"))
      (node (ref "LAN") (pin "A") (pinfunction "A_A") (pintype "passive"))
      (node (ref "LAN") (pin "B") (pinfunction "B_B") (pintype "passive"))
      (node (ref "LCD") (pin "11") (pintype "passive"))
      (node (ref "LCD") (pin "20") (pintype "passive"))
      (node (ref "LCD") (pin "29") (pintype "passive"))
      (node (ref "LCD") (pin "41") (pintype "passive"))
      (node (ref "LED") (pin "2") (pinfunction "K_2") (pintype "passive"))
      (node (ref "R11") (pin "1") (pintype "passive"))
      (node (ref "R14") (pin "2") (pinfunction "2_2") (pintype "passive"))
      (node (ref "R15") (pin "2") (pinfunction "2_2") (pintype "passive"))
      (node (ref "R19") (pin "2") (pinfunction "2_2") (pintype "passive"))
      (node (ref "R20") (pin "2") (pinfunction "2_2") (pintype "passive"))
      (node (ref "RST") (pin "2") (pinfunction "2_2") (pintype "passive"))
      (node (ref "U1") (pin "PA2") (pinfunction "PA2_PA2") (pintype "passive"))
      (node (ref "U1") (pin "PB50") (pinfunction "PB50_PB50") (pintype "passive"))
      (node (ref "U1") (pin "PC56") (pinfunction "PC56_PC56") (pintype "passive"))
      (node (ref "U2") (pin "1") (pinfunction "GND_1") (pintype "passive"))
      (node (ref "U3") (pin "1") (pinfunction "GND_1") (pintype "passive"))
      (node (ref "U4") (pin "15") (pinfunction "VSS_15") (pintype "passive"))
      (node (ref "U5") (pin "14") (pinfunction "RST_14") (pintype "passive"))
      (node (ref "U5") (pin "15") (pinfunction "DGND_15") (pintype "passive"))
      (node (ref "U5") (pin "18") (pinfunction "TEST3_18") (pintype "passive"))
      (node (ref "U5") (pin "19") (pinfunction "TEST4_19") (pintype "passive"))
      (node (ref "U5") (pin "23") (pinfunction "DGND_23") (pintype "passive"))
      (node (ref "U5") (pin "25") (pinfunction "AGND_25") (pintype "passive"))
      (node (ref "U5") (pin "31") (pinfunction "AGND_31") (pintype "passive"))
      (node (ref "U5") (pin "32") (pinfunction "AGND_32") (pintype "passive"))
      (node (ref "U5") (pin "42") (pinfunction "DGND_42") (pintype "passive"))
      (node (ref "U5") (pin "48") (pinfunction "TEST5_48") (pintype "passive"))
      (node (ref "U5") (pin "58") (pinfunction "DGND_58") (pintype "passive"))
      (node (ref "U5") (pin "63") (pinfunction "DGND_63") (pintype "passive"))
      (node (ref "U5") (pin "76") (pinfunction "DGND_76") (pintype "passive"))
      (node (ref "U5") (pin "81") (pinfunction "DGND_81") (pintype "passive"))
      (node (ref "U5") (pin "93") (pinfunction "SA4_93") (pintype "passive"))
      (node (ref "U5") (pin "94") (pinfunction "SA5_94") (pintype "passive"))
      (node (ref "U5") (pin "95") (pinfunction "SA6_95") (pintype "passive"))
      (node (ref "U5") (pin "96") (pinfunction "SA7_96") (pintype "passive"))
      (node (ref "U5") (pin "99") (pinfunction "DGND_99") (pintype "passive"))
      (node (ref "USB-DEVICE") (pin "4") (pinfunction "GND_4") (pintype "passive"))
      (node (ref "USB-HOST") (pin "4") (pinfunction "GND_4") (pintype "passive"))
    )
    (net (code "170") (name "Net-(C20-Pad1)") (class "Default")
      (node (ref "C20") (pin "1") (pintype "passive"))
      (node (ref "R6") (pin "1") (pintype "passive"))
      (node (ref "R7") (pin "1") (pintype "passive"))
    )
    (net (code "171") (name "Net-(C21-Pad1)") (class "Default")
      (node (ref "C21") (pin "1") (pinfunction "1_1") (pintype "passive"))
      (node (ref "LAN") (pin "3") (pintype "passive"))
    )
    (net (code "172") (name "Net-(C22-Pad1)") (class "Default")
      (node (ref "C22") (pin "1") (pinfunction "1_1") (pintype "passive"))
      (node (ref "LAN") (pin "6") (pintype "passive"))
    )
    (net (code "173") (name "Net-(CN1-Pad2)") (class "Default")
      (node (ref "CN1") (pin "2") (pinfunction "2_2") (pintype "passive"))
      (node (ref "SW") (pin "2") (pinfunction "2_2") (pintype "passive"))
    )
    (net (code "174") (name "Net-(LAN-GLEDA)") (class "Default")
      (node (ref "LAN") (pin "9") (pinfunction "GLEDA_9") (pintype "passive"))
      (node (ref "R8") (pin "1") (pinfunction "1_1") (pintype "passive"))
    )
    (net (code "175") (name "Net-(LAN-YLEDA)") (class "Default")
      (node (ref "LAN") (pin "11") (pinfunction "YLEDA_11") (pintype "passive"))
      (node (ref "R9") (pin "1") (pinfunction "1_1") (pintype "passive"))
    )
    (net (code "176") (name "Net-(LED-A)") (class "Default")
      (node (ref "LED") (pin "1") (pinfunction "A_1") (pintype "passive"))
      (node (ref "R1") (pin "1") (pinfunction "1_1") (pintype "passive"))
    )
    (net (code "177") (name "Net-(R20-Pad1)") (class "Default")
      (node (ref "R20") (pin "1") (pinfunction "1_1") (pintype "passive"))
      (node (ref "S1") (pin "4") (pinfunction "4_4") (pintype "passive"))
    )
    (net (code "178") (name "Net-(U4-C1+)") (class "Default")
      (node (ref "C10") (pin "2") (pinfunction "2_2") (pintype "passive"))
      (node (ref "U4") (pin "1") (pinfunction "C1+_1") (pintype "passive"))
    )
    (net (code "179") (name "Net-(U4-C1-)") (class "Default")
      (node (ref "C10") (pin "1") (pinfunction "1_1") (pintype "passive"))
      (node (ref "U4") (pin "3") (pinfunction "C1-_3") (pintype "passive"))
    )
    (net (code "180") (name "Net-(U4-C2+)") (class "Default")
      (node (ref "C11") (pin "2") (pinfunction "2_2") (pintype "passive"))
      (node (ref "U4") (pin "4") (pinfunction "C2+_4") (pintype "passive"))
    )
    (net (code "181") (name "Net-(U4-C2-)") (class "Default")
      (node (ref "C11") (pin "1") (pinfunction "1_1") (pintype "passive"))
      (node (ref "U4") (pin "5") (pinfunction "C2-_5") (pintype "passive"))
    )
    (net (code "182") (name "Net-(U4-V+)") (class "Default")
      (node (ref "C12") (pin "2") (pinfunction "2_2") (pintype "passive"))
      (node (ref "U4") (pin "2") (pinfunction "V+_2") (pintype "passive"))
    )
    (net (code "183") (name "Net-(U4-V-)") (class "Default")
      (node (ref "C13") (pin "2") (pinfunction "2_2") (pintype "passive"))
      (node (ref "U4") (pin "6") (pinfunction "V-_6") (pintype "passive"))
    )
    (net (code "184") (name "Net-(U5-BGRES)") (class "Default")
      (node (ref "R11") (pin "2") (pintype "passive"))
      (node (ref "U5") (pin "26") (pinfunction "BGRES_26") (pintype "passive"))
    )
    (net (code "185") (name "Net-(U5-EECS)") (class "Default")
      (node (ref "R2") (pin "1") (pintype "passive"))
      (node (ref "U5") (pin "67") (pinfunction "EECS_67") (pintype "passive"))
    )
    (net (code "186") (name "Net-(U5-SPEED#)") (class "Default")
      (node (ref "R3") (pin "2") (pintype "passive"))
      (node (ref "U5") (pin "60") (pinfunction "SPEED#_60") (pintype "passive"))
    )
    (net (code "187") (name "Net-(U5-X1_25M)") (class "Default")
      (node (ref "C19") (pin "1") (pintype "passive"))
      (node (ref "U5") (pin "22") (pinfunction "X1_25M_22") (pintype "passive"))
      (node (ref "X1") (pin "2") (pintype "passive"))
    )
    (net (code "188") (name "Net-(U5-X2_25M)") (class "Default")
      (node (ref "C18") (pin "1") (pintype "passive"))
      (node (ref "U5") (pin "21") (pinfunction "X2_25M_21") (pintype "passive"))
      (node (ref "X1") (pin "1") (pintype "passive"))
    )
    (net (code "189") (name "Net-(USB-DEVICE-D+)") (class "Default")
      (node (ref "R16") (pin "2") (pinfunction "2_2") (pintype "passive"))
      (node (ref "R18") (pin "2") (pinfunction "2_2") (pintype "passive"))
      (node (ref "USB-DEVICE") (pin "3") (pinfunction "D+_3") (pintype "passive"))
    )
    (net (code "190") (name "Net-(USB-DEVICE-D-)") (class "Default")
      (node (ref "R17") (pin "2") (pinfunction "2_2") (pintype "passive"))
      (node (ref "R19") (pin "1") (pinfunction "1_1") (pintype "passive"))
      (node (ref "USB-DEVICE") (pin "2") (pinfunction "D-_2") (pintype "passive"))
    )
    (net (code "191") (name "Net-(USB-HOST-D+)") (class "Default")
      (node (ref "R13") (pin "1") (pinfunction "1_1") (pintype "passive"))
      (node (ref "R15") (pin "1") (pinfunction "1_1") (pintype "passive"))
      (node (ref "USB-HOST") (pin "3") (pinfunction "D+_3") (pintype "passive"))
    )
    (net (code "192") (name "Net-(USB-HOST-D-)") (class "Default")
      (node (ref "R12") (pin "1") (pinfunction "1_1") (pintype "passive"))
      (node (ref "R14") (pin "1") (pinfunction "1_1") (pintype "passive"))
      (node (ref "USB-HOST") (pin "2") (pinfunction "D-_2") (pintype "passive"))
    )
    (net (code "193") (name "USB_5V") (class "Default")
      (node (ref "USB-DEVICE") (pin "1") (pinfunction "VBUS_1") (pintype "passive"))
    )
    (net (code "194") (name "VDD5V") (class "Default")
      (node (ref "C1") (pin "1") (pinfunction "1_1") (pintype "passive"))
      (node (ref "C2") (pin "1") (pinfunction "1_1") (pintype "passive"))
      (node (ref "C5") (pin "1") (pinfunction "1_1") (pintype "passive"))
      (node (ref "C6") (pin "1") (pinfunction "1_1") (pintype "passive"))
      (node (ref "J1") (pin "3") (pinfunction "3_3") (pintype "passive"))
      (node (ref "R1") (pin "2") (pinfunction "2_2") (pintype "passive"))
      (node (ref "SW") (pin "3") (pinfunction "3_3") (pintype "passive"))
      (node (ref "U1") (pin "PA1") (pinfunction "PA1_PA1") (pintype "passive"))
      (node (ref "U1") (pin "PB49") (pinfunction "PB49_PB49") (pintype "passive"))
      (node (ref "U1") (pin "PC55") (pinfunction "PC55_PC55") (pintype "passive"))
      (node (ref "U2") (pin "3") (pinfunction "Vin_3") (pintype "passive"))
      (node (ref "U3") (pin "3") (pinfunction "Vin_3") (pintype "passive"))
      (node (ref "USB-HOST") (pin "1") (pinfunction "VBUS_1") (pintype "passive"))
    )
    (net (code "195") (name "VDD18V") (class "Default")
      (node (ref "C7") (pin "1") (pinfunction "1_1") (pintype "passive"))
      (node (ref "C8") (pin "1") (pinfunction "1_1") (pintype "passive"))
      (node (ref "Camera") (pin "19") (pinfunction "19_19") (pintype "passive"))
      (node (ref "U3") (pin "4") (pinfunction "Vout_4") (pintype "passive"))
    )
    (net (code "196") (name "VDD33V") (class "Default")
      (node (ref "C14") (pin "1") (pintype "passive"))
      (node (ref "C15") (pin "1") (pintype "passive"))
      (node (ref "C16") (pin "1") (pintype "passive"))
      (node (ref "C17") (pin "1") (pintype "passive"))
      (node (ref "C3") (pin "1") (pinfunction "1_1") (pintype "passive"))
      (node (ref "C4") (pin "1") (pinfunction "1_1") (pintype "passive"))
      (node (ref "C9") (pin "1") (pinfunction "1_1") (pintype "passive"))
      (node (ref "Camera") (pin "17") (pinfunction "17_17") (pintype "passive"))
      (node (ref "D1") (pin "1") (pinfunction "1_1") (pintype "passive"))
      (node (ref "J1") (pin "1") (pinfunction "1_1") (pintype "passive"))
      (node (ref "R10") (pin "1") (pinfunction "1_1") (pintype "passive"))
      (node (ref "R2") (pin "2") (pintype "passive"))
      (node (ref "R4") (pin "2") (pintype "passive"))
      (node (ref "R5") (pin "2") (pintype "passive"))
      (node (ref "R8") (pin "2") (pinfunction "2_2") (pintype "passive"))
      (node (ref "R9") (pin "2") (pinfunction "2_2") (pintype "passive"))
      (node (ref "U2") (pin "4") (pinfunction "Vout_4") (pintype "passive"))
      (node (ref "U4") (pin "16") (pinfunction "VDD_16") (pintype "passive"))
      (node (ref "U5") (pin "16") (pinfunction "TEST1_16") (pintype "passive"))
      (node (ref "U5") (pin "17") (pinfunction "TEST2_17") (pintype "passive"))
      (node (ref "U5") (pin "20") (pinfunction "DVDD_20") (pintype "passive"))
      (node (ref "U5") (pin "27") (pinfunction "AVDD_27") (pintype "passive"))
      (node (ref "U5") (pin "28") (pinfunction "AVDD_28") (pintype "passive"))
      (node (ref "U5") (pin "35") (pinfunction "AVDD_35") (pintype "passive"))
      (node (ref "U5") (pin "36") (pinfunction "DVDD_36") (pintype "passive"))
      (node (ref "U5") (pin "5") (pinfunction "DVDD_5") (pintype "passive"))
      (node (ref "U5") (pin "55") (pinfunction "DVDD_55") (pintype "passive"))
      (node (ref "U5") (pin "72") (pinfunction "DVDD_72") (pintype "passive"))
      (node (ref "U5") (pin "73") (pinfunction "DVDD_73") (pintype "passive"))
      (node (ref "U5") (pin "90") (pinfunction "DVDD_90") (pintype "passive"))
      (node (ref "U5") (pin "97") (pinfunction "SA8_97") (pintype "passive"))
      (node (ref "U5") (pin "98") (pinfunction "SA9_98") (pintype "passive"))
    )
    (net (code "197") (name "unconnected-(COM0-Pad1)") (class "Default")
      (node (ref "COM0") (pin "1") (pinfunction "1_1") (pintype "passive+no_connect"))
    )
    (net (code "198") (name "unconnected-(COM0-Pad4)") (class "Default")
      (node (ref "COM0") (pin "4") (pinfunction "4_4") (pintype "passive+no_connect"))
    )
    (net (code "199") (name "unconnected-(COM0-Pad6)") (class "Default")
      (node (ref "COM0") (pin "6") (pinfunction "6_6") (pintype "passive+no_connect"))
    )
    (net (code "200") (name "unconnected-(COM0-Pad9)") (class "Default")
      (node (ref "COM0") (pin "9") (pinfunction "9_9") (pintype "passive+no_connect"))
    )
    (net (code "201") (name "unconnected-(LAN-PadC)") (class "Default")
      (node (ref "LAN") (pin "C") (pinfunction "C_C") (pintype "passive+no_connect"))
    )
    (net (code "202") (name "unconnected-(LAN-PadD)") (class "Default")
      (node (ref "LAN") (pin "D") (pinfunction "D_D") (pintype "passive+no_connect"))
    )
    (net (code "203") (name "unconnected-(S1-Pad1)") (class "Default")
      (node (ref "S1") (pin "1") (pinfunction "1_1") (pintype "passive+no_connect"))
    )
    (net (code "204") (name "unconnected-(S1-Pad2)") (class "Default")
      (node (ref "S1") (pin "2") (pinfunction "2_2") (pintype "passive+no_connect"))
    )
    (net (code "205") (name "unconnected-(S1-Pad5)") (class "Default")
      (node (ref "S1") (pin "5") (pinfunction "5_5") (pintype "passive+no_connect"))
    )
    (net (code "206") (name "unconnected-(SW-Pad1)") (class "Default")
      (node (ref "SW") (pin "1") (pinfunction "1_1") (pintype "passive+no_connect"))
    )
    (net (code "207") (name "unconnected-(SW-Pad4)") (class "Default")
      (node (ref "SW") (pin "4") (pinfunction "4_4") (pintype "passive+no_connect"))
    )
    (net (code "208") (name "unconnected-(SW-Pad5)") (class "Default")
      (node (ref "SW") (pin "5") (pinfunction "5_5") (pintype "passive+no_connect"))
    )
    (net (code "209") (name "unconnected-(U2-Vout-Pad2)") (class "Default")
      (node (ref "U2") (pin "2") (pinfunction "Vout_2") (pintype "passive+no_connect"))
    )
    (net (code "210") (name "unconnected-(U3-Vout-Pad2)") (class "Default")
      (node (ref "U3") (pin "2") (pinfunction "Vout_2") (pintype "passive+no_connect"))
    )
    (net (code "211") (name "unconnected-(U5-CLK20MO-Pad59)") (class "Default")
      (node (ref "U5") (pin "59") (pinfunction "CLK20MO_59") (pintype "passive+no_connect"))
    )
    (net (code "212") (name "unconnected-(U5-COL-Pad44)") (class "Default")
      (node (ref "U5") (pin "44") (pinfunction "COL_44") (pintype "passive+no_connect"))
    )
    (net (code "213") (name "unconnected-(U5-CRS-Pad43)") (class "Default")
      (node (ref "U5") (pin "43") (pinfunction "CRS_43") (pintype "passive+no_connect"))
    )
    (net (code "214") (name "unconnected-(U5-DUP#-Pad61)") (class "Default")
      (node (ref "U5") (pin "61") (pinfunction "DUP#_61") (pintype "passive+no_connect"))
    )
    (net (code "215") (name "unconnected-(U5-EECK-Pad66)") (class "Default")
      (node (ref "U5") (pin "66") (pinfunction "EECK_66") (pintype "passive+no_connect"))
    )
    (net (code "216") (name "unconnected-(U5-EEDI-Pad64)") (class "Default")
      (node (ref "U5") (pin "64") (pinfunction "EEDI_64") (pintype "passive+no_connect"))
    )
    (net (code "217") (name "unconnected-(U5-EEDO-Pad65)") (class "Default")
      (node (ref "U5") (pin "65") (pinfunction "EEDO_65") (pintype "passive+no_connect"))
    )
    (net (code "218") (name "unconnected-(U5-GPIO0-Pad68)") (class "Default")
      (node (ref "U5") (pin "68") (pinfunction "GPIO0_68") (pintype "passive+no_connect"))
    )
    (net (code "219") (name "unconnected-(U5-GPIO1-Pad69)") (class "Default")
      (node (ref "U5") (pin "69") (pinfunction "GPIO1_69") (pintype "passive+no_connect"))
    )
    (net (code "220") (name "unconnected-(U5-GPIO2-Pad70)") (class "Default")
      (node (ref "U5") (pin "70") (pinfunction "GPIO2_70") (pintype "passive+no_connect"))
    )
    (net (code "221") (name "unconnected-(U5-GPIO3-Pad71)") (class "Default")
      (node (ref "U5") (pin "71") (pinfunction "GPIO3_71") (pintype "passive+no_connect"))
    )
    (net (code "222") (name "unconnected-(U5-IO16-Pad91)") (class "Default")
      (node (ref "U5") (pin "91") (pinfunction "IO16_91") (pintype "passive+no_connect"))
    )
    (net (code "223") (name "unconnected-(U5-LINK_I-Pad37)") (class "Default")
      (node (ref "U5") (pin "37") (pinfunction "LINK_I_37") (pintype "passive+no_connect"))
    )
    (net (code "224") (name "unconnected-(U5-LINK_O-Pad78)") (class "Default")
      (node (ref "U5") (pin "78") (pinfunction "LINK_O_78") (pintype "passive"))
    )
    (net (code "225") (name "unconnected-(U5-MDC-Pad57)") (class "Default")
      (node (ref "U5") (pin "57") (pinfunction "MDC_57") (pintype "passive+no_connect"))
    )
    (net (code "226") (name "unconnected-(U5-MDIO-Pad56)") (class "Default")
      (node (ref "U5") (pin "56") (pinfunction "MDIO_56") (pintype "passive+no_connect"))
    )
    (net (code "227") (name "unconnected-(U5-NC-Pad74)") (class "Default")
      (node (ref "U5") (pin "74") (pinfunction "NC_74") (pintype "passive+no_connect"))
    )
    (net (code "228") (name "unconnected-(U5-NC-Pad75)") (class "Default")
      (node (ref "U5") (pin "75") (pinfunction "NC_75") (pintype "passive+no_connect"))
    )
    (net (code "229") (name "unconnected-(U5-NC-Pad77)") (class "Default")
      (node (ref "U5") (pin "77") (pinfunction "NC_77") (pintype "passive+no_connect"))
    )
    (net (code "230") (name "unconnected-(U5-RXD0-Pad38)") (class "Default")
      (node (ref "U5") (pin "38") (pinfunction "RXD0_38") (pintype "passive+no_connect"))
    )
    (net (code "231") (name "unconnected-(U5-RXD1-Pad39)") (class "Default")
      (node (ref "U5") (pin "39") (pinfunction "RXD1_39") (pintype "passive+no_connect"))
    )
    (net (code "232") (name "unconnected-(U5-RXD2-Pad40)") (class "Default")
      (node (ref "U5") (pin "40") (pinfunction "RXD2_40") (pintype "passive+no_connect"))
    )
    (net (code "233") (name "unconnected-(U5-RXD3-Pad41)") (class "Default")
      (node (ref "U5") (pin "41") (pinfunction "RXD3_41") (pintype "passive+no_connect"))
    )
    (net (code "234") (name "unconnected-(U5-RX_CLK-Pad47)") (class "Default")
      (node (ref "U5") (pin "47") (pinfunction "RX_CLK_47") (pintype "passive+no_connect"))
    )
    (net (code "235") (name "unconnected-(U5-RX_DV-Pad45)") (class "Default")
      (node (ref "U5") (pin "45") (pinfunction "RX_DV_45") (pintype "passive+no_connect"))
    )
    (net (code "236") (name "unconnected-(U5-RX_ER-Pad46)") (class "Default")
      (node (ref "U5") (pin "46") (pinfunction "RX_ER_46") (pintype "passive+no_connect"))
    )
    (net (code "237") (name "unconnected-(U5-SD-Pad24)") (class "Default")
      (node (ref "U5") (pin "24") (pinfunction "SD_24") (pintype "passive+no_connect"))
    )
    (net (code "238") (name "unconnected-(U5-TXD0-Pad50)") (class "Default")
      (node (ref "U5") (pin "50") (pinfunction "TXD0_50") (pintype "passive+no_connect"))
    )
    (net (code "239") (name "unconnected-(U5-TXD1-Pad51)") (class "Default")
      (node (ref "U5") (pin "51") (pinfunction "TXD1_51") (pintype "passive+no_connect"))
    )
    (net (code "240") (name "unconnected-(U5-TXD2-Pad52)") (class "Default")
      (node (ref "U5") (pin "52") (pinfunction "TXD2_52") (pintype "passive+no_connect"))
    )
    (net (code "241") (name "unconnected-(U5-TXD3-Pad53)") (class "Default")
      (node (ref "U5") (pin "53") (pinfunction "TXD3_53") (pintype "passive+no_connect"))
    )
    (net (code "242") (name "unconnected-(U5-TX_CLK-Pad49)") (class "Default")
      (node (ref "U5") (pin "49") (pinfunction "TX_CLK_49") (pintype "passive+no_connect"))
    )
    (net (code "243") (name "unconnected-(U5-TX_EN-Pad54)") (class "Default")
      (node (ref "U5") (pin "54") (pinfunction "TX_EN_54") (pintype "passive+no_connect"))
    )
    (net (code "244") (name "unconnected-(U5-WACKUP-Pad79)") (class "Default")
      (node (ref "U5") (pin "79") (pinfunction "WACKUP_79") (pintype "passive"))
    )
  )
)
